# small_led_ring.net
KiCad netlist of a schematic drawn in EAGLE
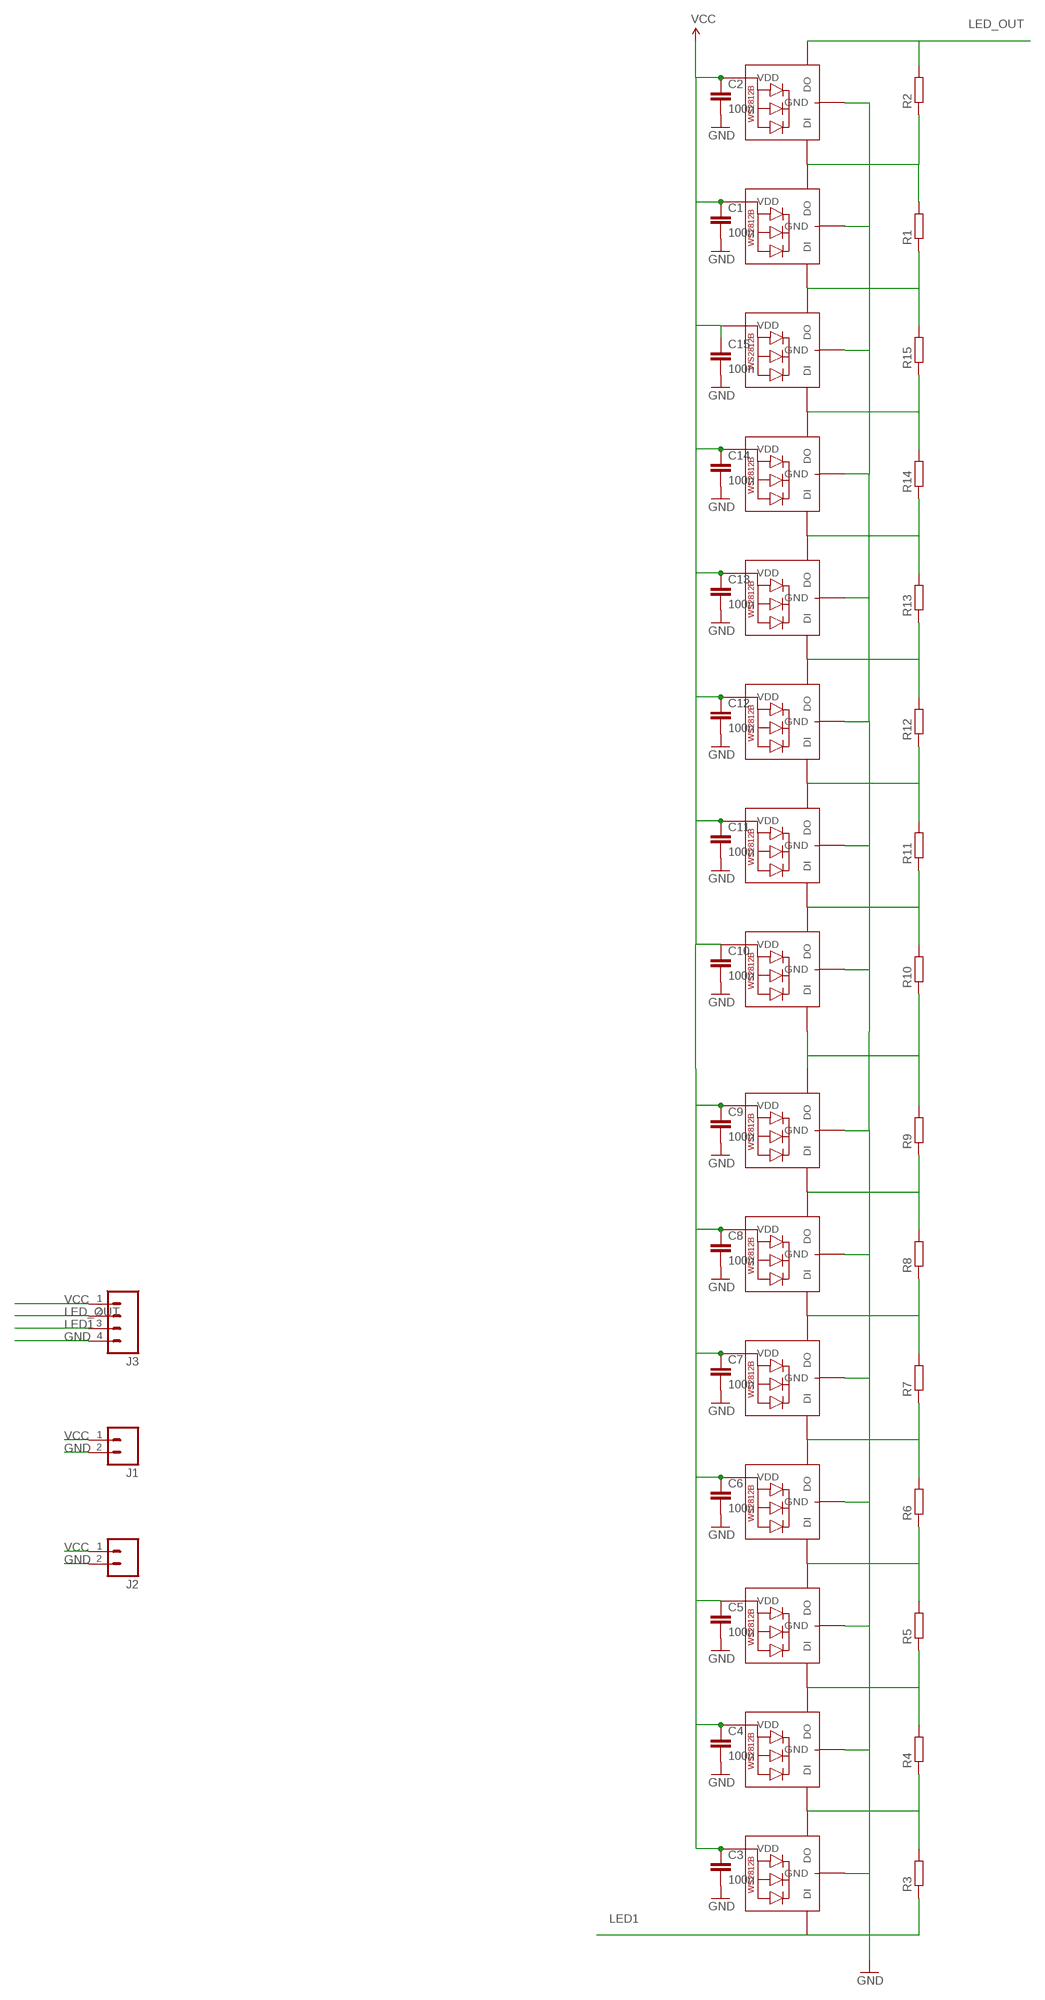
[diagram p0: schematic, sheet 1]

(export (version "E")
  (design (tool "Eeschema 10.0.6"))
  (components
    (comp (ref "C1")
      (value "100n")
      (footprint "eagle-import:0603-CAP")
      (libsource (lib "eagle-import") (part "CAP0603-CAP"))
    )
    (comp (ref "C2")
      (value "100n")
      (footprint "eagle-import:0603-CAP")
      (libsource (lib "eagle-import") (part "CAP0603-CAP"))
    )
    (comp (ref "C3")
      (value "100n")
      (footprint "eagle-import:0603-CAP")
      (libsource (lib "eagle-import") (part "CAP0603-CAP"))
    )
    (comp (ref "C4")
      (value "100n")
      (footprint "eagle-import:0603-CAP")
      (libsource (lib "eagle-import") (part "CAP0603-CAP"))
    )
    (comp (ref "C5")
      (value "100n")
      (footprint "eagle-import:0603-CAP")
      (libsource (lib "eagle-import") (part "CAP0603-CAP"))
    )
    (comp (ref "C6")
      (value "100n")
      (footprint "eagle-import:0603-CAP")
      (libsource (lib "eagle-import") (part "CAP0603-CAP"))
    )
    (comp (ref "C7")
      (value "100n")
      (footprint "eagle-import:0603-CAP")
      (libsource (lib "eagle-import") (part "CAP0603-CAP"))
    )
    (comp (ref "C8")
      (value "100n")
      (footprint "eagle-import:0603-CAP")
      (libsource (lib "eagle-import") (part "CAP0603-CAP"))
    )
    (comp (ref "C9")
      (value "100n")
      (footprint "eagle-import:0603-CAP")
      (libsource (lib "eagle-import") (part "CAP0603-CAP"))
    )
    (comp (ref "C10")
      (value "100n")
      (footprint "eagle-import:0603-CAP")
      (libsource (lib "eagle-import") (part "CAP0603-CAP"))
    )
    (comp (ref "C11")
      (value "100n")
      (footprint "eagle-import:0603-CAP")
      (libsource (lib "eagle-import") (part "CAP0603-CAP"))
    )
    (comp (ref "C12")
      (value "100n")
      (footprint "eagle-import:0603-CAP")
      (libsource (lib "eagle-import") (part "CAP0603-CAP"))
    )
    (comp (ref "C13")
      (value "100n")
      (footprint "eagle-import:0603-CAP")
      (libsource (lib "eagle-import") (part "CAP0603-CAP"))
    )
    (comp (ref "C14")
      (value "100n")
      (footprint "eagle-import:0603-CAP")
      (libsource (lib "eagle-import") (part "CAP0603-CAP"))
    )
    (comp (ref "C15")
      (value "100n")
      (footprint "eagle-import:0603-CAP")
      (libsource (lib "eagle-import") (part "CAP0603-CAP"))
    )
    (comp (ref "J1")
      (value "M021X02_NO_SILK")
      (footprint "eagle-import:1X02_NO_SILK")
      (libsource (lib "eagle-import") (part "M021X02_NO_SILK"))
    )
    (comp (ref "J2")
      (value "M021X02_NO_SILK")
      (footprint "eagle-import:1X02_NO_SILK")
      (libsource (lib "eagle-import") (part "M021X02_NO_SILK"))
    )
    (comp (ref "J3")
      (value "M04NO_SILK_ALL_ROUND")
      (footprint "eagle-import:1X04_NO_SILK_ALL_ROUND")
      (libsource (lib "eagle-import") (part "M04NO_SILK_ALL_ROUND"))
    )
    (comp (ref "LED1")
      (value "WS2812B3535")
      (footprint "eagle-import:LED3535")
      (libsource (lib "eagle-import") (part "WS2812B3535"))
    )
    (comp (ref "LED2")
      (value "WS2812B3535")
      (footprint "eagle-import:LED3535")
      (libsource (lib "eagle-import") (part "WS2812B3535"))
    )
    (comp (ref "LED3")
      (value "WS2812B3535")
      (footprint "eagle-import:LED3535")
      (libsource (lib "eagle-import") (part "WS2812B3535"))
    )
    (comp (ref "LED4")
      (value "WS2812B3535")
      (footprint "eagle-import:LED3535")
      (fields (field (name "SPICEPREFIX") "E"))
      (libsource (lib "eagle-import") (part "WS2812B3535"))
    )
    (comp (ref "LED5")
      (value "WS2812B3535")
      (footprint "eagle-import:LED3535")
      (libsource (lib "eagle-import") (part "WS2812B3535"))
    )
    (comp (ref "LED6")
      (value "WS2812B3535")
      (footprint "eagle-import:LED3535")
      (libsource (lib "eagle-import") (part "WS2812B3535"))
    )
    (comp (ref "LED7")
      (value "WS2812B3535")
      (footprint "eagle-import:LED3535")
      (libsource (lib "eagle-import") (part "WS2812B3535"))
    )
    (comp (ref "LED8")
      (value "WS2812B3535")
      (footprint "eagle-import:LED3535")
      (libsource (lib "eagle-import") (part "WS2812B3535"))
    )
    (comp (ref "LED9")
      (value "WS2812B3535")
      (footprint "eagle-import:LED3535")
      (libsource (lib "eagle-import") (part "WS2812B3535"))
    )
    (comp (ref "LED10")
      (value "WS2812B3535")
      (footprint "eagle-import:LED3535")
      (libsource (lib "eagle-import") (part "WS2812B3535"))
    )
    (comp (ref "LED11")
      (value "WS2812B3535")
      (footprint "eagle-import:LED3535")
      (libsource (lib "eagle-import") (part "WS2812B3535"))
    )
    (comp (ref "LED12")
      (value "WS2812B3535")
      (footprint "eagle-import:LED3535")
      (libsource (lib "eagle-import") (part "WS2812B3535"))
    )
    (comp (ref "LED13")
      (value "WS2812B3535")
      (footprint "eagle-import:LED3535")
      (libsource (lib "eagle-import") (part "WS2812B3535"))
    )
    (comp (ref "LED14")
      (value "WS2812B3535")
      (footprint "eagle-import:LED3535")
      (libsource (lib "eagle-import") (part "WS2812B3535"))
    )
    (comp (ref "LED15")
      (value "WS2812B3535")
      (footprint "eagle-import:LED3535")
      (libsource (lib "eagle-import") (part "WS2812B3535"))
    )
    (comp (ref "R1")
      (value "R-EU_R0603")
      (footprint "eagle-import:R0603")
      (libsource (lib "eagle-import") (part "R-EU_R0603"))
    )
    (comp (ref "R2")
      (value "R-EU_R0603")
      (footprint "eagle-import:R0603")
      (libsource (lib "eagle-import") (part "R-EU_R0603"))
    )
    (comp (ref "R3")
      (value "R-EU_R0603")
      (footprint "eagle-import:R0603")
      (libsource (lib "eagle-import") (part "R-EU_R0603"))
    )
    (comp (ref "R4")
      (value "R-EU_R0603")
      (footprint "eagle-import:R0603")
      (libsource (lib "eagle-import") (part "R-EU_R0603"))
    )
    (comp (ref "R5")
      (value "R-EU_R0603")
      (footprint "eagle-import:R0603")
      (libsource (lib "eagle-import") (part "R-EU_R0603"))
    )
    (comp (ref "R6")
      (value "R-EU_R0603")
      (footprint "eagle-import:R0603")
      (libsource (lib "eagle-import") (part "R-EU_R0603"))
    )
    (comp (ref "R7")
      (value "R-EU_R0603")
      (footprint "eagle-import:R0603")
      (libsource (lib "eagle-import") (part "R-EU_R0603"))
    )
    (comp (ref "R8")
      (value "R-EU_R0603")
      (footprint "eagle-import:R0603")
      (libsource (lib "eagle-import") (part "R-EU_R0603"))
    )
    (comp (ref "R9")
      (value "R-EU_R0603")
      (footprint "eagle-import:R0603")
      (libsource (lib "eagle-import") (part "R-EU_R0603"))
    )
    (comp (ref "R10")
      (value "R-EU_R0603")
      (footprint "eagle-import:R0603")
      (libsource (lib "eagle-import") (part "R-EU_R0603"))
    )
    (comp (ref "R11")
      (value "R-EU_R0603")
      (footprint "eagle-import:R0603")
      (libsource (lib "eagle-import") (part "R-EU_R0603"))
    )
    (comp (ref "R12")
      (value "R-EU_R0603")
      (footprint "eagle-import:R0603")
      (libsource (lib "eagle-import") (part "R-EU_R0603"))
    )
    (comp (ref "R13")
      (value "R-EU_R0603")
      (footprint "eagle-import:R0603")
      (libsource (lib "eagle-import") (part "R-EU_R0603"))
    )
    (comp (ref "R14")
      (value "R-EU_R0603")
      (footprint "eagle-import:R0603")
      (libsource (lib "eagle-import") (part "R-EU_R0603"))
    )
    (comp (ref "R15")
      (value "R-EU_R0603")
      (footprint "eagle-import:R0603")
      (libsource (lib "eagle-import") (part "R-EU_R0603"))
    )
  )
  (nets
    (net (code "1") (name "/LED1") (class "Default")
      (node (ref "J3") (pin "3") (pinfunction "3_3") (pintype "passive"))
      (node (ref "LED1") (pin "1") (pinfunction "DI_1") (pintype "input"))
      (node (ref "R3") (pin "1") (pinfunction "1_1") (pintype "passive"))
    )
    (net (code "2") (name "/LED_OUT") (class "Default")
      (node (ref "J3") (pin "2") (pinfunction "2_2") (pintype "passive"))
      (node (ref "LED15") (pin "3") (pinfunction "DO_3") (pintype "output"))
      (node (ref "R2") (pin "2") (pinfunction "2_2") (pintype "passive"))
    )
    (net (code "3") (name "GND") (class "Default")
      (node (ref "C1") (pin "2") (pinfunction "2_2") (pintype "passive"))
      (node (ref "C10") (pin "2") (pinfunction "2_2") (pintype "passive"))
      (node (ref "C11") (pin "2") (pinfunction "2_2") (pintype "passive"))
      (node (ref "C12") (pin "2") (pinfunction "2_2") (pintype "passive"))
      (node (ref "C13") (pin "2") (pinfunction "2_2") (pintype "passive"))
      (node (ref "C14") (pin "2") (pinfunction "2_2") (pintype "passive"))
      (node (ref "C15") (pin "2") (pinfunction "2_2") (pintype "passive"))
      (node (ref "C2") (pin "2") (pinfunction "2_2") (pintype "passive"))
      (node (ref "C3") (pin "2") (pinfunction "2_2") (pintype "passive"))
      (node (ref "C4") (pin "2") (pinfunction "2_2") (pintype "passive"))
      (node (ref "C5") (pin "2") (pinfunction "2_2") (pintype "passive"))
      (node (ref "C6") (pin "2") (pinfunction "2_2") (pintype "passive"))
      (node (ref "C7") (pin "2") (pinfunction "2_2") (pintype "passive"))
      (node (ref "C8") (pin "2") (pinfunction "2_2") (pintype "passive"))
      (node (ref "C9") (pin "2") (pinfunction "2_2") (pintype "passive"))
      (node (ref "J1") (pin "2") (pinfunction "2_2") (pintype "passive"))
      (node (ref "J2") (pin "2") (pinfunction "2_2") (pintype "passive"))
      (node (ref "J3") (pin "4") (pinfunction "4_4") (pintype "passive"))
      (node (ref "LED1") (pin "4") (pinfunction "GND_4") (pintype "power_in"))
      (node (ref "LED10") (pin "4") (pinfunction "GND_4") (pintype "power_in"))
      (node (ref "LED11") (pin "4") (pinfunction "GND_4") (pintype "power_in"))
      (node (ref "LED12") (pin "4") (pinfunction "GND_4") (pintype "power_in"))
      (node (ref "LED13") (pin "4") (pinfunction "GND_4") (pintype "power_in"))
      (node (ref "LED14") (pin "4") (pinfunction "GND_4") (pintype "power_in"))
      (node (ref "LED15") (pin "4") (pinfunction "GND_4") (pintype "power_in"))
      (node (ref "LED2") (pin "4") (pinfunction "GND_4") (pintype "power_in"))
      (node (ref "LED3") (pin "4") (pinfunction "GND_4") (pintype "power_in"))
      (node (ref "LED4") (pin "4") (pinfunction "GND_4") (pintype "power_in"))
      (node (ref "LED5") (pin "4") (pinfunction "GND_4") (pintype "power_in"))
      (node (ref "LED6") (pin "4") (pinfunction "GND_4") (pintype "power_in"))
      (node (ref "LED7") (pin "4") (pinfunction "GND_4") (pintype "power_in"))
      (node (ref "LED8") (pin "4") (pinfunction "GND_4") (pintype "power_in"))
      (node (ref "LED9") (pin "4") (pinfunction "GND_4") (pintype "power_in"))
    )
    (net (code "4") (name "Net-(LED1-DO)") (class "Default")
      (node (ref "LED1") (pin "3") (pinfunction "DO_3") (pintype "output"))
      (node (ref "LED2") (pin "1") (pinfunction "DI_1") (pintype "input"))
      (node (ref "R3") (pin "2") (pinfunction "2_2") (pintype "passive"))
      (node (ref "R4") (pin "1") (pinfunction "1_1") (pintype "passive"))
    )
    (net (code "5") (name "Net-(LED2-DO)") (class "Default")
      (node (ref "LED2") (pin "3") (pinfunction "DO_3") (pintype "output"))
      (node (ref "LED3") (pin "1") (pinfunction "DI_1") (pintype "input"))
      (node (ref "R4") (pin "2") (pinfunction "2_2") (pintype "passive"))
      (node (ref "R5") (pin "1") (pinfunction "1_1") (pintype "passive"))
    )
    (net (code "6") (name "Net-(LED3-DO)") (class "Default")
      (node (ref "LED3") (pin "3") (pinfunction "DO_3") (pintype "output"))
      (node (ref "LED4") (pin "1") (pinfunction "DI_1") (pintype "input"))
      (node (ref "R5") (pin "2") (pinfunction "2_2") (pintype "passive"))
      (node (ref "R6") (pin "1") (pinfunction "1_1") (pintype "passive"))
    )
    (net (code "7") (name "Net-(LED4-DO)") (class "Default")
      (node (ref "LED4") (pin "3") (pinfunction "DO_3") (pintype "output"))
      (node (ref "LED5") (pin "1") (pinfunction "DI_1") (pintype "input"))
      (node (ref "R6") (pin "2") (pinfunction "2_2") (pintype "passive"))
      (node (ref "R7") (pin "1") (pinfunction "1_1") (pintype "passive"))
    )
    (net (code "8") (name "Net-(LED5-DO)") (class "Default")
      (node (ref "LED5") (pin "3") (pinfunction "DO_3") (pintype "output"))
      (node (ref "LED6") (pin "1") (pinfunction "DI_1") (pintype "input"))
      (node (ref "R7") (pin "2") (pinfunction "2_2") (pintype "passive"))
      (node (ref "R8") (pin "1") (pinfunction "1_1") (pintype "passive"))
    )
    (net (code "9") (name "Net-(LED6-DO)") (class "Default")
      (node (ref "LED6") (pin "3") (pinfunction "DO_3") (pintype "output"))
      (node (ref "LED7") (pin "1") (pinfunction "DI_1") (pintype "input"))
      (node (ref "R8") (pin "2") (pinfunction "2_2") (pintype "passive"))
      (node (ref "R9") (pin "1") (pinfunction "1_1") (pintype "passive"))
    )
    (net (code "10") (name "Net-(LED7-DO)") (class "Default")
      (node (ref "LED7") (pin "3") (pinfunction "DO_3") (pintype "output"))
      (node (ref "LED8") (pin "1") (pinfunction "DI_1") (pintype "input"))
      (node (ref "R10") (pin "1") (pinfunction "1_1") (pintype "passive"))
      (node (ref "R9") (pin "2") (pinfunction "2_2") (pintype "passive"))
    )
    (net (code "11") (name "Net-(LED8-DO)") (class "Default")
      (node (ref "LED8") (pin "3") (pinfunction "DO_3") (pintype "output"))
      (node (ref "LED9") (pin "1") (pinfunction "DI_1") (pintype "input"))
      (node (ref "R10") (pin "2") (pinfunction "2_2") (pintype "passive"))
      (node (ref "R11") (pin "1") (pinfunction "1_1") (pintype "passive"))
    )
    (net (code "12") (name "Net-(LED10-DI)") (class "Default")
      (node (ref "LED10") (pin "1") (pinfunction "DI_1") (pintype "input"))
      (node (ref "LED9") (pin "3") (pinfunction "DO_3") (pintype "output"))
      (node (ref "R11") (pin "2") (pinfunction "2_2") (pintype "passive"))
      (node (ref "R12") (pin "1") (pinfunction "1_1") (pintype "passive"))
    )
    (net (code "13") (name "Net-(LED10-DO)") (class "Default")
      (node (ref "LED10") (pin "3") (pinfunction "DO_3") (pintype "output"))
      (node (ref "LED11") (pin "1") (pinfunction "DI_1") (pintype "input"))
      (node (ref "R12") (pin "2") (pinfunction "2_2") (pintype "passive"))
      (node (ref "R13") (pin "1") (pinfunction "1_1") (pintype "passive"))
    )
    (net (code "14") (name "Net-(LED11-DO)") (class "Default")
      (node (ref "LED11") (pin "3") (pinfunction "DO_3") (pintype "output"))
      (node (ref "LED12") (pin "1") (pinfunction "DI_1") (pintype "input"))
      (node (ref "R13") (pin "2") (pinfunction "2_2") (pintype "passive"))
      (node (ref "R14") (pin "1") (pinfunction "1_1") (pintype "passive"))
    )
    (net (code "15") (name "Net-(LED12-DO)") (class "Default")
      (node (ref "LED12") (pin "3") (pinfunction "DO_3") (pintype "output"))
      (node (ref "LED13") (pin "1") (pinfunction "DI_1") (pintype "input"))
      (node (ref "R14") (pin "2") (pinfunction "2_2") (pintype "passive"))
      (node (ref "R15") (pin "1") (pinfunction "1_1") (pintype "passive"))
    )
    (net (code "16") (name "Net-(LED13-DO)") (class "Default")
      (node (ref "LED13") (pin "3") (pinfunction "DO_3") (pintype "output"))
      (node (ref "LED14") (pin "1") (pinfunction "DI_1") (pintype "input"))
      (node (ref "R1") (pin "1") (pinfunction "1_1") (pintype "passive"))
      (node (ref "R15") (pin "2") (pinfunction "2_2") (pintype "passive"))
    )
    (net (code "17") (name "Net-(LED14-DO)") (class "Default")
      (node (ref "LED14") (pin "3") (pinfunction "DO_3") (pintype "output"))
      (node (ref "LED15") (pin "1") (pinfunction "DI_1") (pintype "input"))
      (node (ref "R1") (pin "2") (pinfunction "2_2") (pintype "passive"))
      (node (ref "R2") (pin "1") (pinfunction "1_1") (pintype "passive"))
    )
    (net (code "18") (name "VCC") (class "Default")
      (node (ref "C1") (pin "1") (pinfunction "1_1") (pintype "passive"))
      (node (ref "C10") (pin "1") (pinfunction "1_1") (pintype "passive"))
      (node (ref "C11") (pin "1") (pinfunction "1_1") (pintype "passive"))
      (node (ref "C12") (pin "1") (pinfunction "1_1") (pintype "passive"))
      (node (ref "C13") (pin "1") (pinfunction "1_1") (pintype "passive"))
      (node (ref "C14") (pin "1") (pinfunction "1_1") (pintype "passive"))
      (node (ref "C15") (pin "1") (pinfunction "1_1") (pintype "passive"))
      (node (ref "C2") (pin "1") (pinfunction "1_1") (pintype "passive"))
      (node (ref "C3") (pin "1") (pinfunction "1_1") (pintype "passive"))
      (node (ref "C4") (pin "1") (pinfunction "1_1") (pintype "passive"))
      (node (ref "C5") (pin "1") (pinfunction "1_1") (pintype "passive"))
      (node (ref "C6") (pin "1") (pinfunction "1_1") (pintype "passive"))
      (node (ref "C7") (pin "1") (pinfunction "1_1") (pintype "passive"))
      (node (ref "C8") (pin "1") (pinfunction "1_1") (pintype "passive"))
      (node (ref "C9") (pin "1") (pinfunction "1_1") (pintype "passive"))
      (node (ref "J1") (pin "1") (pinfunction "1_1") (pintype "passive"))
      (node (ref "J2") (pin "1") (pinfunction "1_1") (pintype "passive"))
      (node (ref "J3") (pin "1") (pinfunction "1_1") (pintype "passive"))
      (node (ref "LED1") (pin "2") (pinfunction "VDD_2") (pintype "power_in"))
      (node (ref "LED10") (pin "2") (pinfunction "VDD_2") (pintype "power_in"))
      (node (ref "LED11") (pin "2") (pinfunction "VDD_2") (pintype "power_in"))
      (node (ref "LED12") (pin "2") (pinfunction "VDD_2") (pintype "power_in"))
      (node (ref "LED13") (pin "2") (pinfunction "VDD_2") (pintype "power_in"))
      (node (ref "LED14") (pin "2") (pinfunction "VDD_2") (pintype "power_in"))
      (node (ref "LED15") (pin "2") (pinfunction "VDD_2") (pintype "power_in"))
      (node (ref "LED2") (pin "2") (pinfunction "VDD_2") (pintype "power_in"))
      (node (ref "LED3") (pin "2") (pinfunction "VDD_2") (pintype "power_in"))
      (node (ref "LED4") (pin "2") (pinfunction "VDD_2") (pintype "power_in"))
      (node (ref "LED5") (pin "2") (pinfunction "VDD_2") (pintype "power_in"))
      (node (ref "LED6") (pin "2") (pinfunction "VDD_2") (pintype "power_in"))
      (node (ref "LED7") (pin "2") (pinfunction "VDD_2") (pintype "power_in"))
      (node (ref "LED8") (pin "2") (pinfunction "VDD_2") (pintype "power_in"))
      (node (ref "LED9") (pin "2") (pinfunction "VDD_2") (pintype "power_in"))
    )
  )
)
